# bt_schield.net
KiCad netlist of a schematic drawn in EAGLE
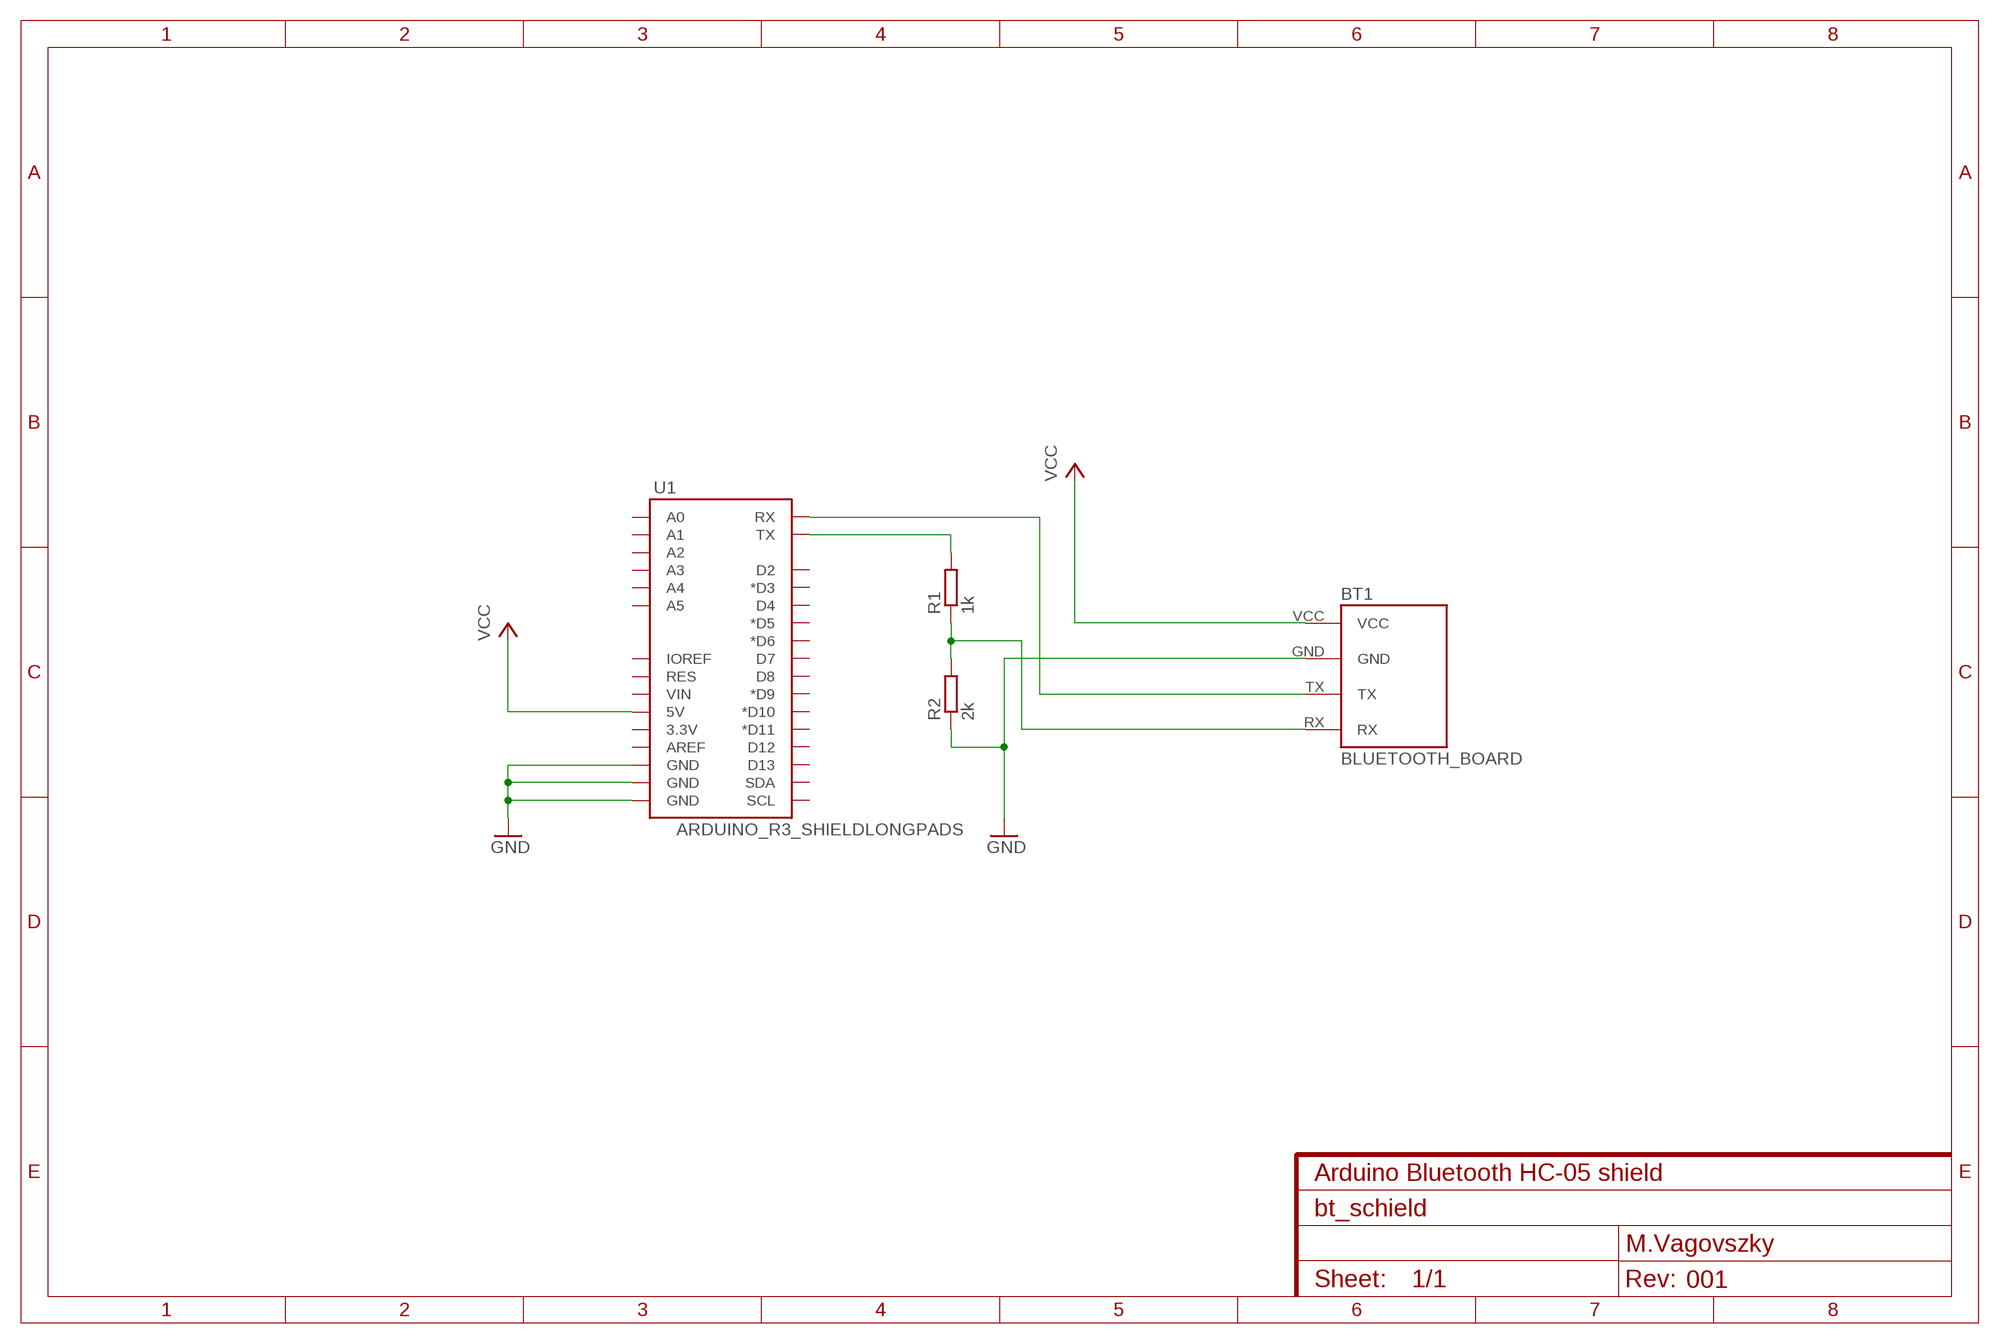
[diagram p0: schematic, sheet 1]

(export (version "E")
  (design (tool "Eeschema 10.0.6"))
  (components
    (comp (ref "BT1")
      (value "BLUETOOTH_BOARD")
      (footprint "eagle-import:BT_BOARD_FOOTPRINT")
      (libsource (lib "eagle-import") (part "BLUETOOTH_BOARD"))
    )
    (comp (ref "R1")
      (value "1k")
      (footprint "eagle-import:0207_12")
      (libsource (lib "eagle-import") (part "R-EU_0207/12"))
    )
    (comp (ref "R2")
      (value "2k")
      (footprint "eagle-import:0207_12")
      (libsource (lib "eagle-import") (part "R-EU_0207/12"))
    )
    (comp (ref "U1")
      (value "ARDUINO_R3_SHIELDLONGPADS")
      (footprint "eagle-import:UNO_R3_SHIELD_LONGPADS")
      (libsource (lib "eagle-import") (part "ARDUINO_R3_SHIELDLONGPADS"))
    )
  )
  (nets
    (net (code "1") (name "GND") (class "Default")
      (node (ref "BT1") (pin "GND") (pinfunction "GND_GND") (pintype "bidirectional"))
      (node (ref "R2") (pin "1") (pinfunction "1_1") (pintype "passive"))
      (node (ref "U1") (pin "GND@0") (pinfunction "GND_GND@0") (pintype "bidirectional"))
      (node (ref "U1") (pin "GND@1") (pinfunction "GND_GND@1") (pintype "bidirectional"))
      (node (ref "U1") (pin "GND@2") (pinfunction "GND_GND@2") (pintype "bidirectional"))
    )
    (net (code "2") (name "Net-(BT1-PadRX)") (class "Default")
      (node (ref "BT1") (pin "RX") (pinfunction "RX_RX") (pintype "bidirectional"))
      (node (ref "R1") (pin "1") (pinfunction "1_1") (pintype "passive"))
      (node (ref "R2") (pin "2") (pinfunction "2_2") (pintype "passive"))
    )
    (net (code "3") (name "Net-(BT1-PadTX)") (class "Default")
      (node (ref "BT1") (pin "TX") (pinfunction "TX_TX") (pintype "bidirectional"))
      (node (ref "U1") (pin "RX") (pinfunction "RX_RX") (pintype "bidirectional"))
    )
    (net (code "4") (name "Net-(R1-Pad2)") (class "Default")
      (node (ref "R1") (pin "2") (pinfunction "2_2") (pintype "passive"))
      (node (ref "U1") (pin "TX") (pinfunction "TX_TX") (pintype "bidirectional"))
    )
    (net (code "5") (name "VCC") (class "Default")
      (node (ref "BT1") (pin "VCC") (pinfunction "VCC_VCC") (pintype "bidirectional"))
      (node (ref "U1") (pin "5V") (pinfunction "5V_5V") (pintype "bidirectional"))
    )
    (net (code "6") (name "unconnected-(U1-*D3-PadD3)") (class "Default")
      (node (ref "U1") (pin "D3") (pinfunction "*D3_D3") (pintype "bidirectional"))
    )
    (net (code "7") (name "unconnected-(U1-*D5-PadD5)") (class "Default")
      (node (ref "U1") (pin "D5") (pinfunction "*D5_D5") (pintype "bidirectional"))
    )
    (net (code "8") (name "unconnected-(U1-*D6-PadD6)") (class "Default")
      (node (ref "U1") (pin "D6") (pinfunction "*D6_D6") (pintype "bidirectional"))
    )
    (net (code "9") (name "unconnected-(U1-*D9-PadD9)") (class "Default")
      (node (ref "U1") (pin "D9") (pinfunction "*D9_D9") (pintype "bidirectional"))
    )
    (net (code "10") (name "unconnected-(U1-*D10-PadD10)") (class "Default")
      (node (ref "U1") (pin "D10") (pinfunction "*D10_D10") (pintype "bidirectional"))
    )
    (net (code "11") (name "unconnected-(U1-*D11-PadD11)") (class "Default")
      (node (ref "U1") (pin "D11") (pinfunction "*D11_D11") (pintype "bidirectional"))
    )
    (net (code "12") (name "unconnected-(U1-Pad3.3V)") (class "Default")
      (node (ref "U1") (pin "3.3V") (pinfunction "3.3V_3.3V") (pintype "bidirectional"))
    )
    (net (code "13") (name "unconnected-(U1-PadA0)") (class "Default")
      (node (ref "U1") (pin "A0") (pinfunction "A0_A0") (pintype "bidirectional"))
    )
    (net (code "14") (name "unconnected-(U1-PadA1)") (class "Default")
      (node (ref "U1") (pin "A1") (pinfunction "A1_A1") (pintype "bidirectional"))
    )
    (net (code "15") (name "unconnected-(U1-PadA2)") (class "Default")
      (node (ref "U1") (pin "A2") (pinfunction "A2_A2") (pintype "bidirectional"))
    )
    (net (code "16") (name "unconnected-(U1-PadA3)") (class "Default")
      (node (ref "U1") (pin "A3") (pinfunction "A3_A3") (pintype "bidirectional"))
    )
    (net (code "17") (name "unconnected-(U1-PadA4)") (class "Default")
      (node (ref "U1") (pin "A4") (pinfunction "A4_A4") (pintype "bidirectional"))
    )
    (net (code "18") (name "unconnected-(U1-PadA5)") (class "Default")
      (node (ref "U1") (pin "A5") (pinfunction "A5_A5") (pintype "bidirectional"))
    )
    (net (code "19") (name "unconnected-(U1-PadAREF)") (class "Default")
      (node (ref "U1") (pin "AREF") (pinfunction "AREF_AREF") (pintype "bidirectional"))
    )
    (net (code "20") (name "unconnected-(U1-PadD2)") (class "Default")
      (node (ref "U1") (pin "D2") (pinfunction "D2_D2") (pintype "bidirectional"))
    )
    (net (code "21") (name "unconnected-(U1-PadD4)") (class "Default")
      (node (ref "U1") (pin "D4") (pinfunction "D4_D4") (pintype "bidirectional"))
    )
    (net (code "22") (name "unconnected-(U1-PadD7)") (class "Default")
      (node (ref "U1") (pin "D7") (pinfunction "D7_D7") (pintype "bidirectional"))
    )
    (net (code "23") (name "unconnected-(U1-PadD8)") (class "Default")
      (node (ref "U1") (pin "D8") (pinfunction "D8_D8") (pintype "bidirectional"))
    )
    (net (code "24") (name "unconnected-(U1-PadD12)") (class "Default")
      (node (ref "U1") (pin "D12") (pinfunction "D12_D12") (pintype "bidirectional"))
    )
    (net (code "25") (name "unconnected-(U1-PadD13)") (class "Default")
      (node (ref "U1") (pin "D13") (pinfunction "D13_D13") (pintype "bidirectional"))
    )
    (net (code "26") (name "unconnected-(U1-PadIOREF)") (class "Default")
      (node (ref "U1") (pin "IOREF") (pinfunction "IOREF_IOREF") (pintype "bidirectional"))
    )
    (net (code "27") (name "unconnected-(U1-PadRES)") (class "Default")
      (node (ref "U1") (pin "RES") (pinfunction "RES_RES") (pintype "bidirectional"))
    )
    (net (code "28") (name "unconnected-(U1-PadSCL)") (class "Default")
      (node (ref "U1") (pin "SCL") (pinfunction "SCL_SCL") (pintype "bidirectional"))
    )
    (net (code "29") (name "unconnected-(U1-PadSDA)") (class "Default")
      (node (ref "U1") (pin "SDA") (pinfunction "SDA_SDA") (pintype "bidirectional"))
    )
    (net (code "30") (name "unconnected-(U1-PadVIN)") (class "Default")
      (node (ref "U1") (pin "VIN") (pinfunction "VIN_VIN") (pintype "bidirectional"))
    )
  )
)
